# Spark.net
KiCad netlist of a schematic drawn in EAGLE
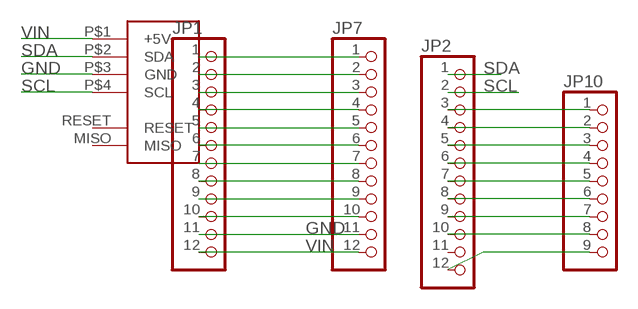
[diagram p0: schematic, sheet 1]

(export (version "E")
  (design (tool "Eeschema 10.0.6"))
  (components
    (comp (ref "JP1")
      (value "PINHD-1X12-CB")
      (footprint "eagle-import:1X12-CB")
      (libsource (lib "eagle-import") (part "PINHD-1X12-CB"))
    )
    (comp (ref "JP2")
      (value "PINHD-1X12-CB")
      (footprint "eagle-import:1X12-CB")
      (libsource (lib "eagle-import") (part "PINHD-1X12-CB"))
    )
    (comp (ref "JP7")
      (value "PINHD-1X12-CB")
      (footprint "eagle-import:1X12-CB")
      (libsource (lib "eagle-import") (part "PINHD-1X12-CB"))
    )
    (comp (ref "JP10")
      (value "PINHD-1X9")
      (footprint "eagle-import:1X09-BIG")
      (libsource (lib "eagle-import") (part "PINHD-1X9"))
    )
    (comp (ref "U$1")
      (value "FOOTPRINTDOUBLE")
      (footprint "eagle-import:FOOTPRINT-DOUBLE")
      (libsource (lib "eagle-import") (part "FOOTPRINTDOUBLE"))
    )
  )
  (nets
    (net (code "1") (name "/GND") (class "Default")
      (node (ref "JP1") (pin "2") (pinfunction "2_2") (pintype "passive"))
      (node (ref "JP7") (pin "2") (pinfunction "2_2") (pintype "passive"))
      (node (ref "U$1") (pin "P$3") (pinfunction "GND_P$3") (pintype "power_in"))
    )
    (net (code "2") (name "/SCL") (class "Default")
      (node (ref "JP2") (pin "2") (pinfunction "2_2") (pintype "passive"))
      (node (ref "U$1") (pin "P$4") (pinfunction "SCL_P$4") (pintype "bidirectional"))
    )
    (net (code "3") (name "/SDA") (class "Default")
      (node (ref "JP2") (pin "1") (pinfunction "1_1") (pintype "passive"))
      (node (ref "U$1") (pin "P$2") (pinfunction "SDA_P$2") (pintype "bidirectional"))
    )
    (net (code "4") (name "/VIN") (class "Default")
      (node (ref "JP1") (pin "1") (pinfunction "1_1") (pintype "passive"))
      (node (ref "JP7") (pin "1") (pinfunction "1_1") (pintype "passive"))
      (node (ref "U$1") (pin "P$1") (pinfunction "+5V_P$1") (pintype "power_in"))
    )
    (net (code "5") (name "Net-(JP1-Pad3)") (class "Default")
      (node (ref "JP1") (pin "3") (pinfunction "3_3") (pintype "passive"))
      (node (ref "JP7") (pin "3") (pinfunction "3_3") (pintype "passive"))
    )
    (net (code "6") (name "Net-(JP1-Pad4)") (class "Default")
      (node (ref "JP1") (pin "4") (pinfunction "4_4") (pintype "passive"))
      (node (ref "JP7") (pin "4") (pinfunction "4_4") (pintype "passive"))
    )
    (net (code "7") (name "Net-(JP1-Pad5)") (class "Default")
      (node (ref "JP1") (pin "5") (pinfunction "5_5") (pintype "passive"))
      (node (ref "JP7") (pin "5") (pinfunction "5_5") (pintype "passive"))
    )
    (net (code "8") (name "Net-(JP1-Pad6)") (class "Default")
      (node (ref "JP1") (pin "6") (pinfunction "6_6") (pintype "passive"))
      (node (ref "JP7") (pin "6") (pinfunction "6_6") (pintype "passive"))
    )
    (net (code "9") (name "Net-(JP1-Pad7)") (class "Default")
      (node (ref "JP1") (pin "7") (pinfunction "7_7") (pintype "passive"))
      (node (ref "JP7") (pin "7") (pinfunction "7_7") (pintype "passive"))
    )
    (net (code "10") (name "Net-(JP1-Pad8)") (class "Default")
      (node (ref "JP1") (pin "8") (pinfunction "8_8") (pintype "passive"))
      (node (ref "JP7") (pin "8") (pinfunction "8_8") (pintype "passive"))
    )
    (net (code "11") (name "Net-(JP1-Pad9)") (class "Default")
      (node (ref "JP1") (pin "9") (pinfunction "9_9") (pintype "passive"))
      (node (ref "JP7") (pin "9") (pinfunction "9_9") (pintype "passive"))
    )
    (net (code "12") (name "Net-(JP1-Pad10)") (class "Default")
      (node (ref "JP1") (pin "10") (pinfunction "10_10") (pintype "passive"))
      (node (ref "JP7") (pin "10") (pinfunction "10_10") (pintype "passive"))
    )
    (net (code "13") (name "Net-(JP1-Pad11)") (class "Default")
      (node (ref "JP1") (pin "11") (pinfunction "11_11") (pintype "passive"))
      (node (ref "JP7") (pin "11") (pinfunction "11_11") (pintype "passive"))
    )
    (net (code "14") (name "Net-(JP1-Pad12)") (class "Default")
      (node (ref "JP1") (pin "12") (pinfunction "12_12") (pintype "passive"))
      (node (ref "JP7") (pin "12") (pinfunction "12_12") (pintype "passive"))
    )
    (net (code "15") (name "Net-(JP10-Pad1)") (class "Default")
      (node (ref "JP10") (pin "1") (pinfunction "1_1") (pintype "passive"))
      (node (ref "JP2") (pin "3") (pinfunction "3_3") (pintype "passive"))
    )
    (net (code "16") (name "Net-(JP10-Pad2)") (class "Default")
      (node (ref "JP10") (pin "2") (pinfunction "2_2") (pintype "passive"))
      (node (ref "JP2") (pin "4") (pinfunction "4_4") (pintype "passive"))
    )
    (net (code "17") (name "Net-(JP10-Pad3)") (class "Default")
      (node (ref "JP10") (pin "3") (pinfunction "3_3") (pintype "passive"))
      (node (ref "JP2") (pin "5") (pinfunction "5_5") (pintype "passive"))
    )
    (net (code "18") (name "Net-(JP10-Pad4)") (class "Default")
      (node (ref "JP10") (pin "4") (pinfunction "4_4") (pintype "passive"))
      (node (ref "JP2") (pin "6") (pinfunction "6_6") (pintype "passive"))
    )
    (net (code "19") (name "Net-(JP10-Pad5)") (class "Default")
      (node (ref "JP10") (pin "5") (pinfunction "5_5") (pintype "passive"))
      (node (ref "JP2") (pin "7") (pinfunction "7_7") (pintype "passive"))
    )
    (net (code "20") (name "Net-(JP10-Pad6)") (class "Default")
      (node (ref "JP10") (pin "6") (pinfunction "6_6") (pintype "passive"))
      (node (ref "JP2") (pin "8") (pinfunction "8_8") (pintype "passive"))
    )
    (net (code "21") (name "Net-(JP10-Pad7)") (class "Default")
      (node (ref "JP10") (pin "7") (pinfunction "7_7") (pintype "passive"))
      (node (ref "JP2") (pin "9") (pinfunction "9_9") (pintype "passive"))
    )
    (net (code "22") (name "Net-(JP10-Pad8)") (class "Default")
      (node (ref "JP10") (pin "8") (pinfunction "8_8") (pintype "passive"))
      (node (ref "JP2") (pin "10") (pinfunction "10_10") (pintype "passive"))
    )
    (net (code "23") (name "Net-(JP10-Pad9)") (class "Default")
      (node (ref "JP10") (pin "9") (pinfunction "9_9") (pintype "passive"))
      (node (ref "JP2") (pin "12") (pinfunction "12_12") (pintype "passive"))
    )
    (net (code "24") (name "unconnected-(JP2-Pad11)") (class "Default")
      (node (ref "JP2") (pin "11") (pinfunction "11_11") (pintype "passive"))
    )
    (net (code "25") (name "unconnected-(U$1-PadMISO)") (class "Default")
      (node (ref "U$1") (pin "MISO") (pinfunction "MISO_MISO") (pintype "bidirectional"))
    )
    (net (code "26") (name "unconnected-(U$1-PadRESET)") (class "Default")
      (node (ref "U$1") (pin "RESET") (pinfunction "RESET_RESET") (pintype "bidirectional"))
    )
  )
)
